# BatteryBoard_2_0.net
KiCad netlist of a schematic drawn in EAGLE
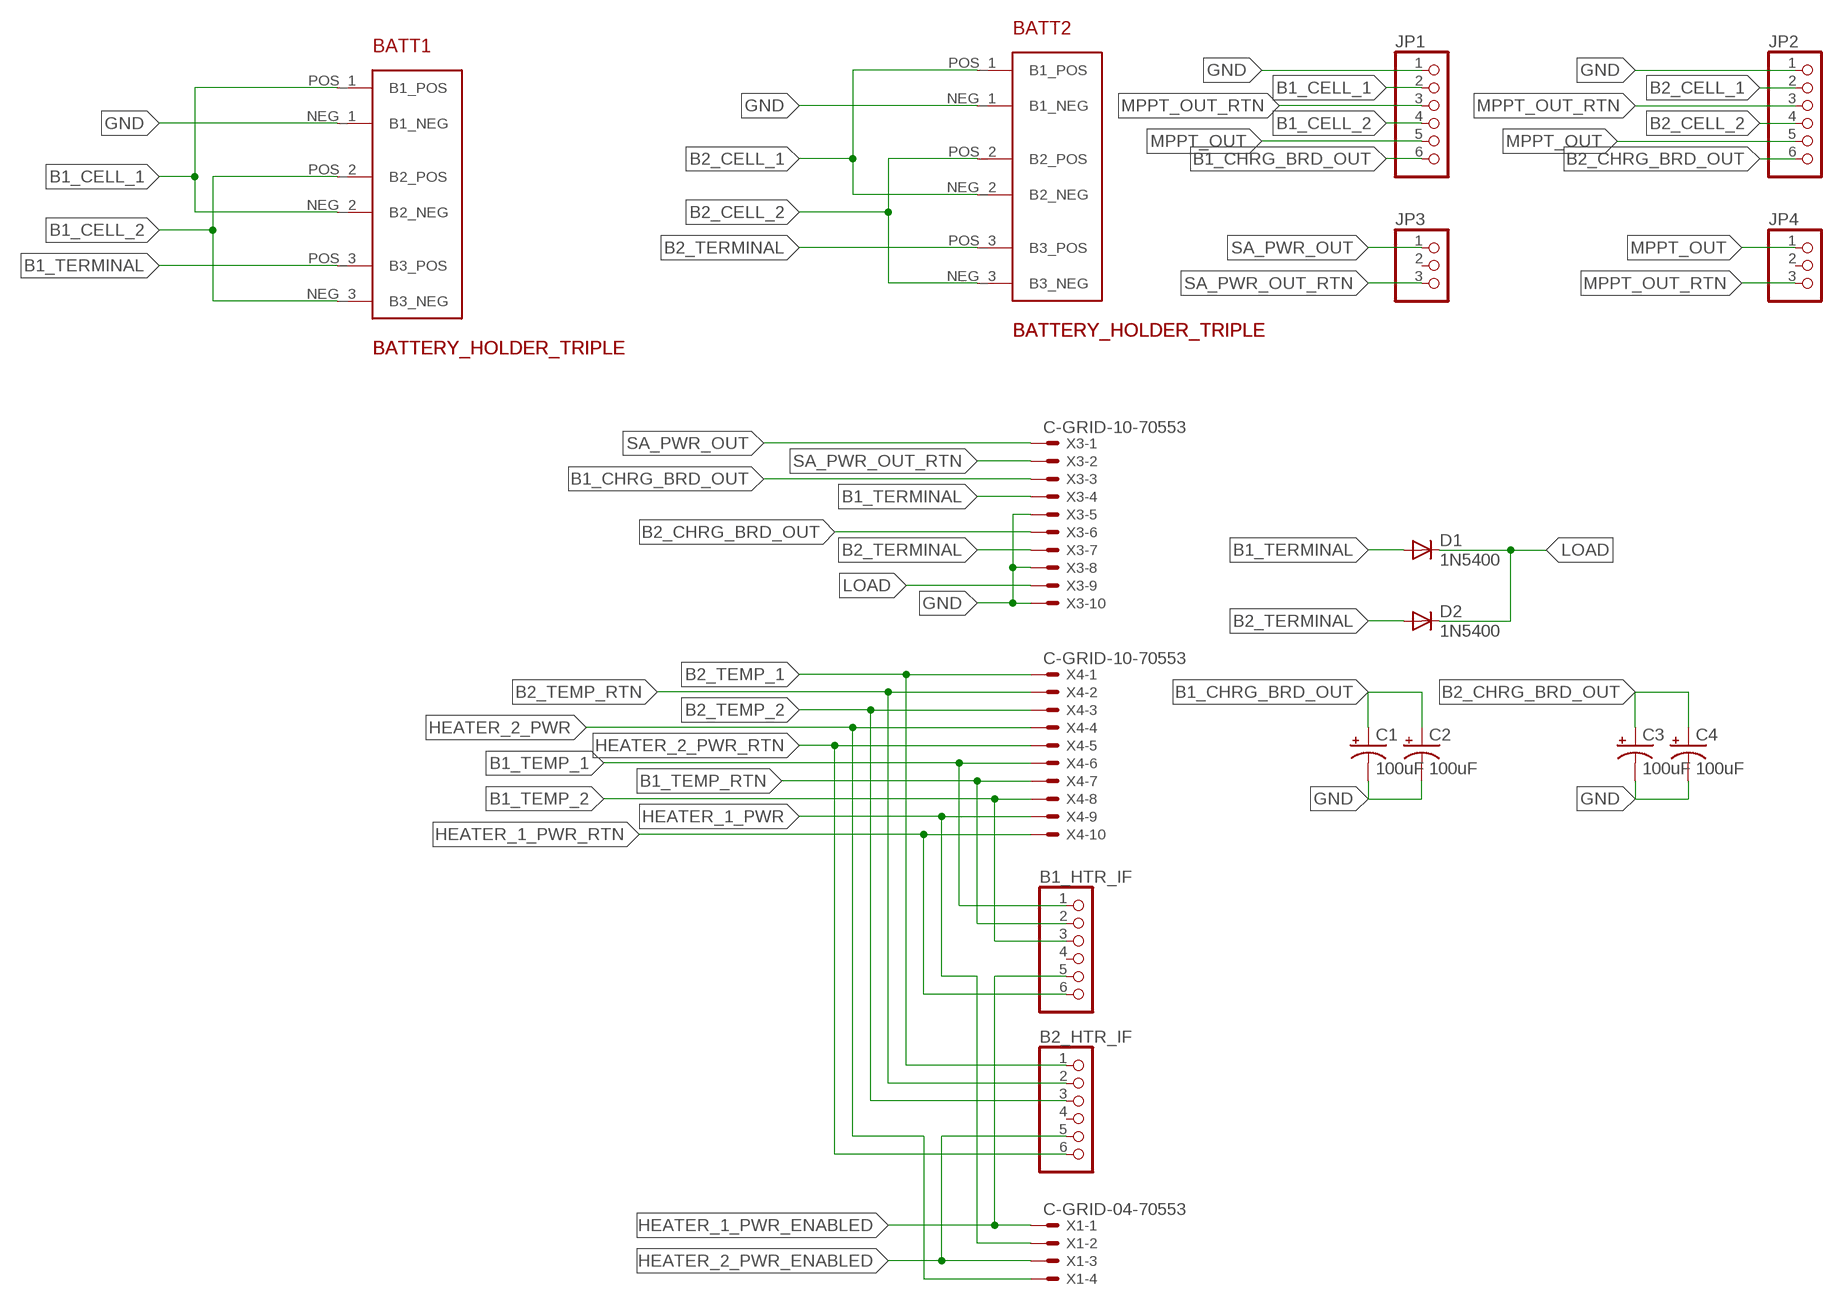
[diagram p0: schematic, sheet 1]

(export (version "E")
  (design (tool "Eeschema 10.0.6"))
  (components
    (comp (ref "B1_HTR_IF")
      (value "PINHD-1X6CLEAN")
      (footprint "eagle-import:1X06-CLEAN")
      (libsource (lib "eagle-import") (part "PINHD-1X6CLEAN"))
    )
    (comp (ref "B2_HTR_IF")
      (value "PINHD-1X6CLEAN")
      (footprint "eagle-import:1X06-CLEAN")
      (libsource (lib "eagle-import") (part "PINHD-1X6CLEAN"))
    )
    (comp (ref "BATT1")
      (value "BATTERY_HOLDER_TRIPLE")
      (footprint "eagle-import:BATT_HOLDER_SINGLE")
      (libsource (lib "eagle-import") (part "BATTERY_HOLDER_TRIPLE"))
    )
    (comp (ref "BATT2")
      (value "BATTERY_HOLDER_TRIPLE")
      (footprint "eagle-import:BATT_HOLDER_SINGLE")
      (libsource (lib "eagle-import") (part "BATTERY_HOLDER_TRIPLE"))
    )
    (comp (ref "C1")
      (value "100uF")
      (footprint "eagle-import:CT7343")
      (libsource (lib "eagle-import") (part "CPOL-USCT7343"))
    )
    (comp (ref "C2")
      (value "100uF")
      (footprint "eagle-import:CT7343")
      (libsource (lib "eagle-import") (part "CPOL-USCT7343"))
    )
    (comp (ref "C3")
      (value "100uF")
      (footprint "eagle-import:CT7343")
      (libsource (lib "eagle-import") (part "CPOL-USCT7343"))
    )
    (comp (ref "C4")
      (value "100uF")
      (footprint "eagle-import:CT7343")
      (libsource (lib "eagle-import") (part "CPOL-USCT7343"))
    )
    (comp (ref "D1")
      (value "1N5400")
      (footprint "eagle-import:DO201-15")
      (libsource (lib "eagle-import") (part "1N5400"))
    )
    (comp (ref "D2")
      (value "1N5400")
      (footprint "eagle-import:DO201-15")
      (libsource (lib "eagle-import") (part "1N5400"))
    )
    (comp (ref "JP1")
      (value "PINHD-1X6CLEAN")
      (footprint "eagle-import:1X06-CLEAN")
      (libsource (lib "eagle-import") (part "PINHD-1X6CLEAN"))
    )
    (comp (ref "JP2")
      (value "PINHD-1X6CLEAN")
      (footprint "eagle-import:1X06-CLEAN")
      (libsource (lib "eagle-import") (part "PINHD-1X6CLEAN"))
    )
    (comp (ref "JP3")
      (value "PINHD-1X3")
      (footprint "eagle-import:1X03")
      (libsource (lib "eagle-import") (part "PINHD-1X3"))
    )
    (comp (ref "JP4")
      (value "PINHD-1X3")
      (footprint "eagle-import:1X03")
      (libsource (lib "eagle-import") (part "PINHD-1X3"))
    )
    (comp (ref "X1")
      (value "C-GRID-04-70553")
      (footprint "eagle-import:70553-04")
      (libsource (lib "eagle-import") (part "C-GRID-04-70553"))
    )
    (comp (ref "X3")
      (value "C-GRID-10-70553")
      (footprint "eagle-import:70553-10")
      (libsource (lib "eagle-import") (part "C-GRID-10-70553"))
    )
    (comp (ref "X4")
      (value "C-GRID-10-70553")
      (footprint "eagle-import:70553-10")
      (libsource (lib "eagle-import") (part "C-GRID-10-70553"))
    )
  )
  (nets
    (net (code "1") (name "B1_CELL_1") (class "Default")
      (node (ref "BATT1") (pin "NEG_2") (pinfunction "B2_NEG_NEG_2") (pintype "bidirectional"))
      (node (ref "BATT1") (pin "POS_1") (pinfunction "B1_POS_POS_1") (pintype "bidirectional"))
      (node (ref "JP1") (pin "2") (pinfunction "2_2") (pintype "passive"))
    )
    (net (code "2") (name "B1_CELL_2") (class "Default")
      (node (ref "BATT1") (pin "NEG_3") (pinfunction "B3_NEG_NEG_3") (pintype "bidirectional"))
      (node (ref "BATT1") (pin "POS_2") (pinfunction "B2_POS_POS_2") (pintype "bidirectional"))
      (node (ref "JP1") (pin "4") (pinfunction "4_4") (pintype "passive"))
    )
    (net (code "3") (name "B1_CHRG_BRD_OUT") (class "Default")
      (node (ref "C1") (pin "+") (pinfunction "+_+") (pintype "passive"))
      (node (ref "C2") (pin "+") (pinfunction "+_+") (pintype "passive"))
      (node (ref "JP1") (pin "6") (pinfunction "6_6") (pintype "passive"))
      (node (ref "X3") (pin "3") (pinfunction "S_3") (pintype "passive"))
    )
    (net (code "4") (name "B1_TEMP_1") (class "Default")
      (node (ref "B1_HTR_IF") (pin "1") (pinfunction "1_1") (pintype "passive"))
      (node (ref "X4") (pin "6") (pinfunction "S_6") (pintype "passive"))
    )
    (net (code "5") (name "B1_TEMP_2") (class "Default")
      (node (ref "B1_HTR_IF") (pin "3") (pinfunction "3_3") (pintype "passive"))
      (node (ref "X4") (pin "8") (pinfunction "S_8") (pintype "passive"))
    )
    (net (code "6") (name "B1_TEMP_RTN") (class "Default")
      (node (ref "B1_HTR_IF") (pin "2") (pinfunction "2_2") (pintype "passive"))
      (node (ref "X4") (pin "7") (pinfunction "S_7") (pintype "passive"))
    )
    (net (code "7") (name "B1_TERMINAL") (class "Default")
      (node (ref "BATT1") (pin "POS_3") (pinfunction "B3_POS_POS_3") (pintype "bidirectional"))
      (node (ref "D1") (pin "A") (pinfunction "A_A") (pintype "passive"))
      (node (ref "X3") (pin "4") (pinfunction "S_4") (pintype "passive"))
    )
    (net (code "8") (name "B2_CELL_1") (class "Default")
      (node (ref "BATT2") (pin "NEG_2") (pinfunction "B2_NEG_NEG_2") (pintype "bidirectional"))
      (node (ref "BATT2") (pin "POS_1") (pinfunction "B1_POS_POS_1") (pintype "bidirectional"))
      (node (ref "JP2") (pin "2") (pinfunction "2_2") (pintype "passive"))
    )
    (net (code "9") (name "B2_CELL_2") (class "Default")
      (node (ref "BATT2") (pin "NEG_3") (pinfunction "B3_NEG_NEG_3") (pintype "bidirectional"))
      (node (ref "BATT2") (pin "POS_2") (pinfunction "B2_POS_POS_2") (pintype "bidirectional"))
      (node (ref "JP2") (pin "4") (pinfunction "4_4") (pintype "passive"))
    )
    (net (code "10") (name "B2_CHRG_BRD_OUT") (class "Default")
      (node (ref "C3") (pin "+") (pinfunction "+_+") (pintype "passive"))
      (node (ref "C4") (pin "+") (pinfunction "+_+") (pintype "passive"))
      (node (ref "JP2") (pin "6") (pinfunction "6_6") (pintype "passive"))
      (node (ref "X3") (pin "6") (pinfunction "S_6") (pintype "passive"))
    )
    (net (code "11") (name "B2_TEMP_1") (class "Default")
      (node (ref "B2_HTR_IF") (pin "1") (pinfunction "1_1") (pintype "passive"))
      (node (ref "X4") (pin "1") (pinfunction "S_1") (pintype "passive"))
    )
    (net (code "12") (name "B2_TEMP_2") (class "Default")
      (node (ref "B2_HTR_IF") (pin "3") (pinfunction "3_3") (pintype "passive"))
      (node (ref "X4") (pin "3") (pinfunction "S_3") (pintype "passive"))
    )
    (net (code "13") (name "B2_TEMP_RTN") (class "Default")
      (node (ref "B2_HTR_IF") (pin "2") (pinfunction "2_2") (pintype "passive"))
      (node (ref "X4") (pin "2") (pinfunction "S_2") (pintype "passive"))
    )
    (net (code "14") (name "B2_TERMINAL") (class "Default")
      (node (ref "BATT2") (pin "POS_3") (pinfunction "B3_POS_POS_3") (pintype "bidirectional"))
      (node (ref "D2") (pin "A") (pinfunction "A_A") (pintype "passive"))
      (node (ref "X3") (pin "7") (pinfunction "S_7") (pintype "passive"))
    )
    (net (code "15") (name "GND") (class "Default")
      (node (ref "BATT1") (pin "NEG_1") (pinfunction "B1_NEG_NEG_1") (pintype "bidirectional"))
      (node (ref "BATT2") (pin "NEG_1") (pinfunction "B1_NEG_NEG_1") (pintype "bidirectional"))
      (node (ref "C1") (pin "-") (pinfunction "-_-") (pintype "passive"))
      (node (ref "C2") (pin "-") (pinfunction "-_-") (pintype "passive"))
      (node (ref "C3") (pin "-") (pinfunction "-_-") (pintype "passive"))
      (node (ref "C4") (pin "-") (pinfunction "-_-") (pintype "passive"))
      (node (ref "JP1") (pin "1") (pinfunction "1_1") (pintype "passive"))
      (node (ref "JP2") (pin "1") (pinfunction "1_1") (pintype "passive"))
      (node (ref "X3") (pin "10") (pinfunction "S_10") (pintype "passive"))
      (node (ref "X3") (pin "5") (pinfunction "S_5") (pintype "passive"))
      (node (ref "X3") (pin "8") (pinfunction "S_8") (pintype "passive"))
    )
    (net (code "16") (name "HEATER_1_PWR") (class "Default")
      (node (ref "X1") (pin "2") (pinfunction "S_2") (pintype "passive"))
      (node (ref "X4") (pin "9") (pinfunction "S_9") (pintype "passive"))
    )
    (net (code "17") (name "HEATER_1_PWR_ENABLED") (class "Default")
      (node (ref "B1_HTR_IF") (pin "5") (pinfunction "5_5") (pintype "passive"))
      (node (ref "X1") (pin "1") (pinfunction "S_1") (pintype "passive"))
    )
    (net (code "18") (name "HEATER_1_PWR_RTN") (class "Default")
      (node (ref "B1_HTR_IF") (pin "6") (pinfunction "6_6") (pintype "passive"))
      (node (ref "X4") (pin "10") (pinfunction "S_10") (pintype "passive"))
    )
    (net (code "19") (name "HEATER_2_PWR") (class "Default")
      (node (ref "X1") (pin "4") (pinfunction "S_4") (pintype "passive"))
      (node (ref "X4") (pin "4") (pinfunction "S_4") (pintype "passive"))
    )
    (net (code "20") (name "HEATER_2_PWR_ENABLED") (class "Default")
      (node (ref "B2_HTR_IF") (pin "5") (pinfunction "5_5") (pintype "passive"))
      (node (ref "X1") (pin "3") (pinfunction "S_3") (pintype "passive"))
    )
    (net (code "21") (name "HEATER_2_PWR_RTN") (class "Default")
      (node (ref "B2_HTR_IF") (pin "6") (pinfunction "6_6") (pintype "passive"))
      (node (ref "X4") (pin "5") (pinfunction "S_5") (pintype "passive"))
    )
    (net (code "22") (name "LOAD") (class "Default")
      (node (ref "D1") (pin "C") (pinfunction "C_C") (pintype "passive"))
      (node (ref "D2") (pin "C") (pinfunction "C_C") (pintype "passive"))
      (node (ref "X3") (pin "9") (pinfunction "S_9") (pintype "passive"))
    )
    (net (code "23") (name "MPPT_OUT") (class "Default")
      (node (ref "JP1") (pin "5") (pinfunction "5_5") (pintype "passive"))
      (node (ref "JP2") (pin "5") (pinfunction "5_5") (pintype "passive"))
      (node (ref "JP4") (pin "1") (pinfunction "1_1") (pintype "passive"))
    )
    (net (code "24") (name "MPPT_OUT_RTN") (class "Default")
      (node (ref "JP1") (pin "3") (pinfunction "3_3") (pintype "passive"))
      (node (ref "JP2") (pin "3") (pinfunction "3_3") (pintype "passive"))
      (node (ref "JP4") (pin "3") (pinfunction "3_3") (pintype "passive"))
    )
    (net (code "25") (name "SA_PWR_OUT") (class "Default")
      (node (ref "JP3") (pin "1") (pinfunction "1_1") (pintype "passive"))
      (node (ref "X3") (pin "1") (pinfunction "S_1") (pintype "passive"))
    )
    (net (code "26") (name "SA_PWR_OUT_RTN") (class "Default")
      (node (ref "JP3") (pin "3") (pinfunction "3_3") (pintype "passive"))
      (node (ref "X3") (pin "2") (pinfunction "S_2") (pintype "passive"))
    )
    (net (code "27") (name "unconnected-(B1_HTR_IF-Pad4)") (class "Default")
      (node (ref "B1_HTR_IF") (pin "4") (pinfunction "4_4") (pintype "passive"))
    )
    (net (code "28") (name "unconnected-(B2_HTR_IF-Pad4)") (class "Default")
      (node (ref "B2_HTR_IF") (pin "4") (pinfunction "4_4") (pintype "passive"))
    )
    (net (code "29") (name "unconnected-(JP3-Pad2)") (class "Default")
      (node (ref "JP3") (pin "2") (pinfunction "2_2") (pintype "passive"))
    )
    (net (code "30") (name "unconnected-(JP4-Pad2)") (class "Default")
      (node (ref "JP4") (pin "2") (pinfunction "2_2") (pintype "passive"))
    )
  )
)
